# roboproj_q3.net
KiCad netlist of a schematic drawn in EAGLE
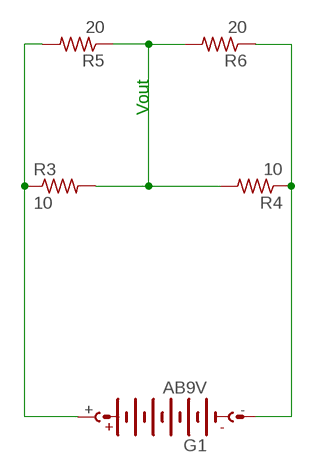
[diagram p0: schematic, sheet 1]

(export (version "E")
  (design (tool "Eeschema 10.0.6"))
  (components
    (comp (ref "G1")
      (value "AB9V")
      (footprint "eagle-import:AB9V")
      (libsource (lib "eagle-import") (part "AB9V"))
    )
    (comp (ref "R3")
      (value "10")
      (footprint "eagle-import:R0805")
      (libsource (lib "eagle-import") (part "R-US_R0805"))
    )
    (comp (ref "R4")
      (value "10")
      (footprint "eagle-import:R0805")
      (libsource (lib "eagle-import") (part "R-US_R0805"))
    )
    (comp (ref "R5")
      (value "20")
      (footprint "eagle-import:R0805")
      (libsource (lib "eagle-import") (part "R-US_R0805"))
    )
    (comp (ref "R6")
      (value "20")
      (footprint "eagle-import:R0805")
      (libsource (lib "eagle-import") (part "R-US_R0805"))
    )
  )
  (nets
    (net (code "1") (name "Net-(G1-Pad+)") (class "Default")
      (node (ref "G1") (pin "+") (pinfunction "+_+") (pintype "passive"))
      (node (ref "R3") (pin "1") (pinfunction "1_1") (pintype "passive"))
      (node (ref "R5") (pin "2") (pinfunction "2_2") (pintype "passive"))
    )
    (net (code "2") (name "Net-(G1-Pad-)") (class "Default")
      (node (ref "G1") (pin "-") (pinfunction "-_-") (pintype "passive"))
      (node (ref "R4") (pin "1") (pinfunction "1_1") (pintype "passive"))
      (node (ref "R6") (pin "1") (pinfunction "1_1") (pintype "passive"))
    )
    (net (code "3") (name "Net-(R3-Pad2)") (class "Default")
      (node (ref "R3") (pin "2") (pinfunction "2_2") (pintype "passive"))
      (node (ref "R4") (pin "2") (pinfunction "2_2") (pintype "passive"))
      (node (ref "R5") (pin "1") (pinfunction "1_1") (pintype "passive"))
      (node (ref "R6") (pin "2") (pinfunction "2_2") (pintype "passive"))
    )
  )
)
